# 105358-3SC001-02_CPU_BRD.net
KiCad netlist of a schematic drawn in Altium Designer
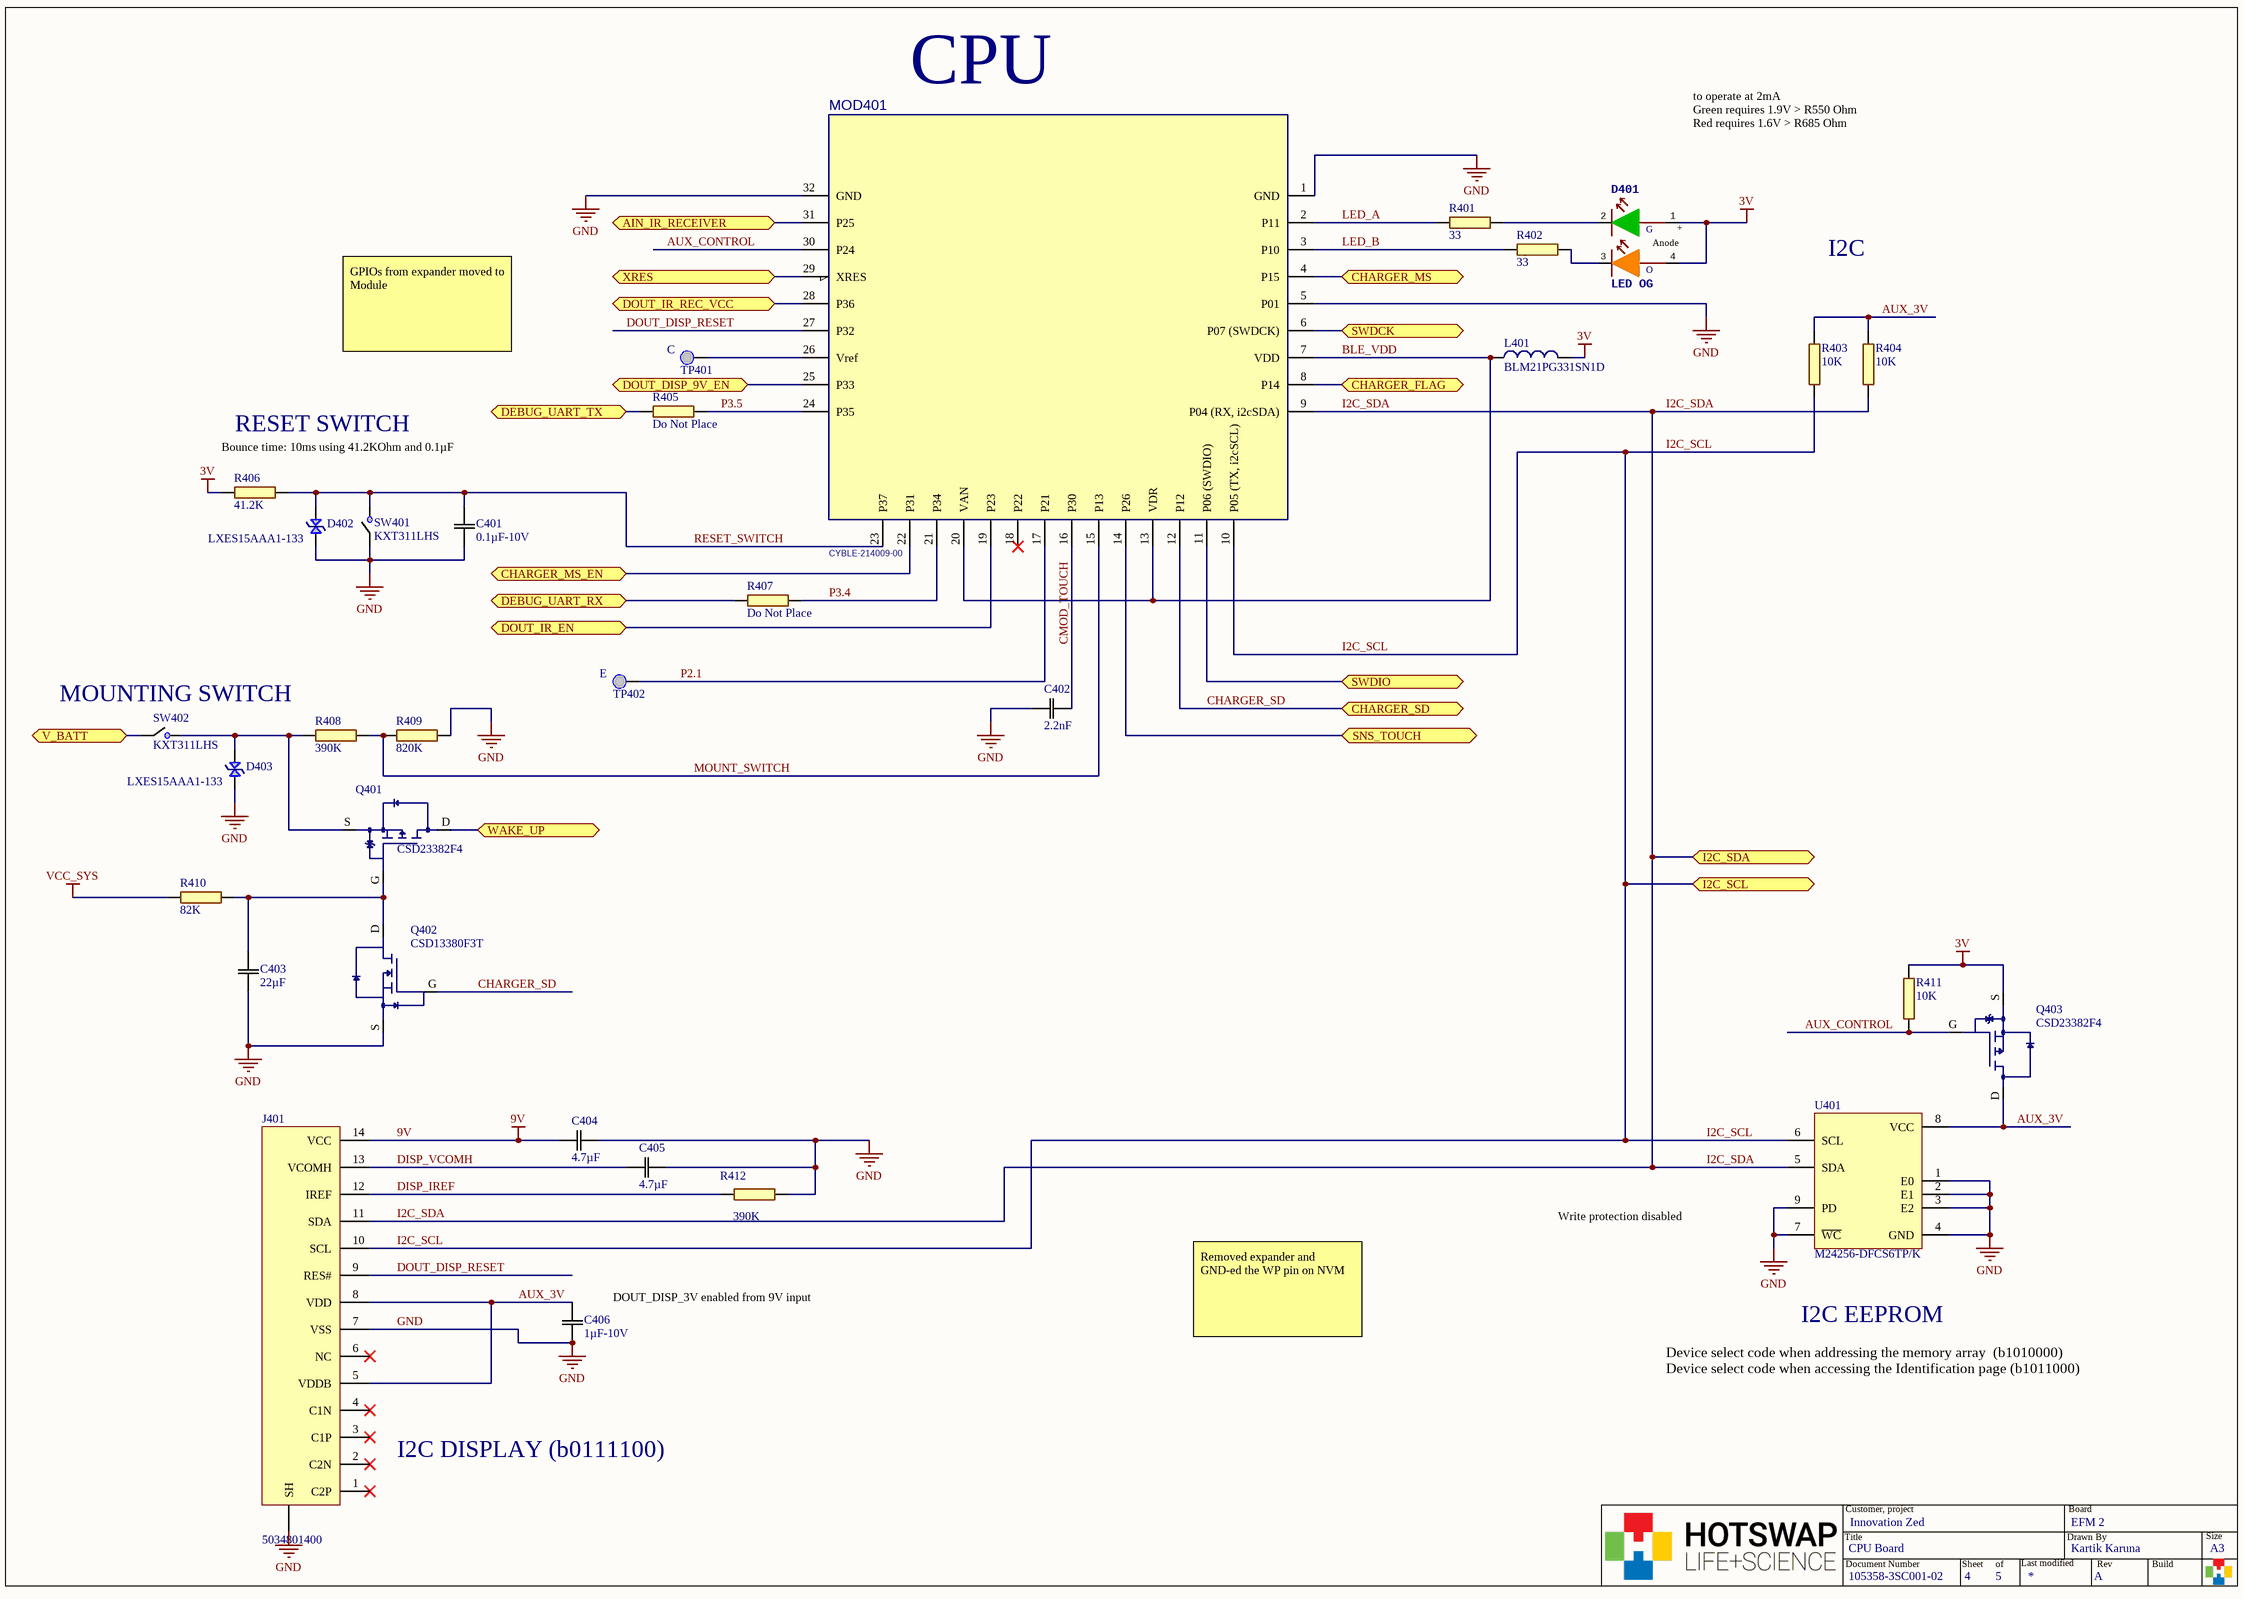
[diagram p0: 105358-3SC001-02_CPU_BRD.SchDoc]

(export (version "E")
  (design (tool "Eeschema 10.0.6"))
  (components
    (comp (ref "C401")
      (value "0.1µF-10V")
      (footprint "0402C_HIGH_DENSITY")
      (description "0.1µF ±10% 10V X5R Ceramic Capacitor 0402")
      (fields
        (field (name "MANUFACTURER PART NUMBER") "CC0402KRX5R6BB104")
        (field (name "MANUFACTURER") "Yageo")
      )
      (libsource (lib "ConnectMedical") (part "0402C-0.1uF-10V"))
    )
    (comp (ref "C402")
      (value "2.2nF")
      (footprint "0402C_HIGH_DENSITY")
      (description "2.2nF ±10% 50V X5R Ceramic Capacitor 0402")
      (fields
        (field (name "MANUFACTURER PART NUMBER") "GRM155R61H222KA01D")
        (field (name "MANUFACTURER") "Murata Electronics North America")
      )
      (libsource (lib "ConnectMedical") (part "0402C-2.2nF-50V"))
    )
    (comp (ref "C403")
      (value "22µF")
      (footprint "0603C-GENERIC")
      (description "22µF ±20% 10V Ceramic Capacitor X5R 0603")
      (fields
        (field (name "MANUFACTURER PART NUMBER") "C1608X5R1A226M080AC")
        (field (name "MANUFACTURER") "TDK Corporation")
      )
      (libsource (lib "ConnectMedical") (part "0603C-22uF-10V"))
    )
    (comp (ref "C404")
      (value "4.7µF")
      (footprint "0402C_HIGH_DENSITY")
      (description "4.7µF ±10% 6.3V X5R Ceramic Capacitor 0402")
      (fields
        (field (name "MANUFACTURER PART NUMBER") "C1005X5R0J475K050BC")
        (field (name "MANUFACTURER") "TDK Corporation")
      )
      (libsource (lib "ConnectMedical") (part "0402C-4.7uF-6.3V"))
    )
    (comp (ref "C405")
      (value "4.7µF")
      (footprint "0402C_HIGH_DENSITY")
      (description "4.7µF ±10% 6.3V X5R Ceramic Capacitor 0402")
      (fields
        (field (name "MANUFACTURER PART NUMBER") "C1005X5R0J475K050BC")
        (field (name "MANUFACTURER") "TDK Corporation")
      )
      (libsource (lib "ConnectMedical") (part "0402C-4.7uF-6.3V"))
    )
    (comp (ref "C406")
      (value "1µF-10V")
      (footprint "0402C_HIGH_DENSITY")
      (description "1µF ±10% 10V X5R Ceramic Capacitor 0402")
      (fields
        (field (name "MANUFACTURER PART NUMBER") "CC0402KRX5R6BB105")
        (field (name "MANUFACTURER") "Yageo")
      )
      (libsource (lib "ConnectMedical") (part "0402C-1uF-10V"))
    )
    (comp (ref "D401")
      (value "LED OG")
      (footprint "KPHBM-2012CGKSEKC")
      (description "LED GRN/ORNG")
      (fields
        (field (name "MANUFACTURER") "Kingbright")
        (field (name "MANUFACTURER PART NUMBER") "KPHBM-2012CGKSEKC")
      )
      (libsource (lib "ConnectMedical") (part "LED GRN/ORNG 570NM 601NM"))
    )
    (comp (ref "D402")
      (value "LXES15AAA1-133")
      (footprint "0402C-GENERIC")
      (description "TVS DIODE 15VWM 0402")
      (fields
        (field (name "MANUFACTURER") "Murata Electronics North America")
        (field (name "DIGI-KEY PART NUMBER") "490-13209-1-ND")
      )
      (libsource (lib "ConnectMedical") (part "TVS DIODE 15VWM 0402"))
    )
    (comp (ref "D403")
      (value "LXES15AAA1-133")
      (footprint "0402C-GENERIC")
      (description "TVS DIODE 15VWM 0402")
      (fields
        (field (name "MANUFACTURER") "Murata Electronics North America")
        (field (name "DIGI-KEY PART NUMBER") "490-13209-1-ND")
      )
      (libsource (lib "ConnectMedical") (part "TVS DIODE 15VWM 0402"))
    )
    (comp (ref "J401")
      (value "5034801400")
      (footprint "5034801400")
      (description "Connector molex to OLED Display")
      (fields (field (name "MANUFACTURER") "Molex, LLC") (field (name "DIGI-KEY PART NUMBER") "WM1442CT-ND"))
      (libsource (lib "ConnectMedical") (part "Molex-5034801400"))
    )
    (comp (ref "L401")
      (value "BLM21PG331SN1D")
      (footprint "0805L_HIGH_DENSITY - Hybrid 0402")
      (description "0805 Ferrite Bead 330Ohm@100MHz")
      (fields
        (field (name "DIGI-KEY PART NUMBER") "490-5988-1-ND")
        (field (name "MANUFACTURER") "Murata Electronics North America")
      )
      (libsource (lib "ConnectMedical") (part "BLM21PG331SN1D"))
    )
    (comp (ref "MOD401")
      (value "CYBLE-214009-00")
      (footprint "CYBLE-014008-00_MinKeepOut")
      (description "BLE PSoC Module 4.1")
      (fields
        (field (name "MANUFACTURER") "Cypress Semiconductor Corp")
        (field (name "DIGI-KEY PART NUMBER") "428-3809-ND")
      )
      (libsource (lib "ConnectMedical") (part "CYBLE-214009-00"))
    )
    (comp (ref "Q401")
      (value "CSD23382F4")
      (footprint "CSD23382F4 -DFN65P100X35-3L")
      (description "MOSFET P-CH 12V 22A 3PICOSTAR")
      (fields
        (field (name "DIGI-KEY PART NUMBER") "296-40003-1-ND")
        (field (name "MANUFACTURER") "Texas Instruments")
      )
      (libsource (lib "ConnectMedical") (part "CSD23382F4"))
    )
    (comp (ref "Q402")
      (value "CSD13380F3T")
      (footprint "CSD13380F3-DFN40P69X35-3L")
      (description "12V N-CHANNEL FEMTOFET MOSFET")
      (fields (field (name "MANUFACTURER") "Texas Instruments"))
      (libsource (lib "ConnectMedical") (part "CSD13380F3T"))
    )
    (comp (ref "Q403")
      (value "CSD23382F4")
      (footprint "CSD23382F4 -DFN65P100X35-3L")
      (description "MOSFET P-CH 12V 22A 3PICOSTAR")
      (fields
        (field (name "DIGI-KEY PART NUMBER") "296-40003-1-ND")
        (field (name "MANUFACTURER") "Texas Instruments")
      )
      (libsource (lib "ConnectMedical") (part "CSD23382F4"))
    )
    (comp (ref "R401")
      (value "33")
      (footprint "0402R-GENERIC")
      (description "RES SMD  33 OHM 1% 1/16W 0402")
      (fields (field (name "DIGI-KEY PART NUMBER") "311-33.0LRCT-ND") (field (name "MANUFACTURER") "Yageo"))
      (libsource (lib "ConnectMedical") (part "0402R- 33 OHM-1%-0.063W"))
    )
    (comp (ref "R402")
      (value "33")
      (footprint "0402R-GENERIC")
      (description "RES SMD  33 OHM 1% 1/16W 0402")
      (fields (field (name "DIGI-KEY PART NUMBER") "311-33.0LRCT-ND") (field (name "MANUFACTURER") "Yageo"))
      (libsource (lib "ConnectMedical") (part "0402R- 33 OHM-1%-0.063W"))
    )
    (comp (ref "R403")
      (value "10K")
      (footprint "0402R-GENERIC")
      (description "RES SMD 10kOHM 1% 1/16W 0402")
      (fields (field (name "DIGI-KEY PART NUMBER") "311-10.0KLRCT-ND") (field (name "MANUFACTURER") "Yageo"))
      (libsource (lib "ConnectMedical") (part "0402R-10k OHM-1%-0.063W"))
    )
    (comp (ref "R404")
      (value "10K")
      (footprint "0402R-GENERIC")
      (description "RES SMD 10kOHM 1% 1/16W 0402")
      (fields (field (name "DIGI-KEY PART NUMBER") "311-10.0KLRCT-ND") (field (name "MANUFACTURER") "Yageo"))
      (libsource (lib "ConnectMedical") (part "0402R-10k OHM-1%-0.063W"))
    )
    (comp (ref "R405")
      (value "Do Not Place")
      (footprint "0402R-GENERIC")
      (libsource (lib "ConnectMedical") (part "0402R-Do Not Place"))
    )
    (comp (ref "R406")
      (value "41.2K")
      (footprint "0402R-GENERIC")
      (description "RES SMD 41.2kOHM 1% 1/16W 0402")
      (fields (field (name "DIGI-KEY PART NUMBER") "YAG3155CT-ND") (field (name "MANUFACTURER") "Yageo"))
      (libsource (lib "ConnectMedical") (part "0402R-41.2k OHM-1%-0.063W"))
    )
    (comp (ref "R407")
      (value "Do Not Place")
      (footprint "0402R-GENERIC")
      (libsource (lib "ConnectMedical") (part "0402R-Do Not Place"))
    )
    (comp (ref "R408")
      (value "390K")
      (footprint "0402R-GENERIC")
      (description "RES SMD 390kOHM 1% 1/16W 0402")
      (fields (field (name "DIGI-KEY PART NUMBER") "YAG3143CT-ND") (field (name "MANUFACTURER") "Yageo"))
      (libsource (lib "ConnectMedical") (part "0402R-390k OHM-1%-0.063W"))
    )
    (comp (ref "R409")
      (value "820K")
      (footprint "0402R-GENERIC")
      (description "RES SMD 820kOHM 1% 1/16W 0402")
      (fields (field (name "DIGI-KEY PART NUMBER") "YAG3240CT-ND") (field (name "MANUFACTURER") "Yageo"))
      (libsource (lib "ConnectMedical") (part "0402R-820k OHM-1%-0.063W"))
    )
    (comp (ref "R410")
      (value "82K")
      (footprint "0402R-GENERIC")
      (description "RES SMD 82kOHM 1% 1/16W 0402")
      (fields (field (name "DIGI-KEY PART NUMBER") "311-82.0KLRCT-ND") (field (name "MANUFACTURER") "Yageo"))
      (libsource (lib "ConnectMedical") (part "0402R-82k OHM-1%-0.063W"))
    )
    (comp (ref "R411")
      (value "10K")
      (footprint "0402R-GENERIC")
      (description "RES SMD 10kOHM 1% 1/16W 0402")
      (fields (field (name "DIGI-KEY PART NUMBER") "311-10.0KLRCT-ND") (field (name "MANUFACTURER") "Yageo"))
      (libsource (lib "ConnectMedical") (part "0402R-10k OHM-1%-0.063W"))
    )
    (comp (ref "R412")
      (value "390K")
      (footprint "0402R-GENERIC")
      (description "RES SMD 390kOHM 1% 1/16W 0402")
      (fields (field (name "DIGI-KEY PART NUMBER") "YAG3143CT-ND") (field (name "MANUFACTURER") "Yageo"))
      (libsource (lib "ConnectMedical") (part "0402R-390k OHM-1%-0.063W"))
    )
    (comp (ref "SW401")
      (value "KXT311LHS")
      (footprint "KXT311LHS_B")
      (description "SPST Tactile Switch")
      (fields (field (name "MANUFACTURER PART NUMBER") "KXT 311 LHS") (field (name "MANUFACTURER") "C&K"))
      (libsource (lib "ConnectMedical") (part "KXT311LHS"))
    )
    (comp (ref "SW402")
      (value "KXT311LHS")
      (footprint "KXT311LHS_B")
      (description "SPST Tactile Switch")
      (fields (field (name "MANUFACTURER PART NUMBER") "KXT 311 LHS") (field (name "MANUFACTURER") "C&K"))
      (libsource (lib "ConnectMedical") (part "KXT311LHS"))
    )
    (comp (ref "TP401")
      (value "TEST POINT")
      (footprint "PAD TEST POINT")
      (description "Testing Poiny")
      (libsource (lib "ConnectMedical") (part "TEST POINT"))
    )
    (comp (ref "TP402")
      (value "TEST POINT")
      (footprint "PAD TEST POINT")
      (description "Testing Poiny")
      (libsource (lib "ConnectMedical") (part "TEST POINT"))
    )
    (comp (ref "U401")
      (value "M24256-DFCS6TP/K")
      (footprint "UFDFPN8-M24256-DFMC6TG")
      (description "IC EEPROM 256KBIT 400KHZ 8UFDFPN")
      (fields
        (field (name "MANUFACTURER PART NUMBER") "M24256-DFMC6TG")
        (field (name "MANUFACTURER") "STMicroelectronics")
      )
      (libsource (lib "ConnectMedical") (part "M24256-DFMC6TG"))
    )
  )
  (nets
    (net (code "1") (name "/AIN_IR_RECEIVER") (class "Default")
      (node (ref "MOD401") (pin "31") (pinfunction "P25_31") (pintype "passive"))
    )
    (net (code "2") (name "/AUX_3V") (class "Default")
      (node (ref "C406") (pin "2") (pinfunction "2_2") (pintype "passive"))
      (node (ref "J401") (pin "5") (pinfunction "VDDB_5") (pintype "passive"))
      (node (ref "J401") (pin "8") (pinfunction "VDD_8") (pintype "passive"))
      (node (ref "Q403") (pin "D") (pinfunction "3_D") (pintype "passive"))
      (node (ref "R403") (pin "1") (pintype "passive"))
      (node (ref "R404") (pin "1") (pintype "passive"))
      (node (ref "U401") (pin "8") (pinfunction "VCC_8") (pintype "passive"))
    )
    (net (code "3") (name "/AUX_CONTROL") (class "Default")
      (node (ref "MOD401") (pin "30") (pinfunction "P24_30") (pintype "passive"))
      (node (ref "Q403") (pin "G") (pinfunction "1_G") (pintype "passive"))
      (node (ref "R411") (pin "2") (pintype "passive"))
    )
    (net (code "4") (name "/BLE_VDD") (class "Default")
      (node (ref "L401") (pin "1") (pinfunction "1_1") (pintype "passive"))
      (node (ref "MOD401") (pin "13") (pinfunction "VDR_13") (pintype "power_in"))
      (node (ref "MOD401") (pin "20") (pinfunction "VAN_20") (pintype "power_in"))
      (node (ref "MOD401") (pin "7") (pinfunction "VDD_7") (pintype "power_in"))
    )
    (net (code "5") (name "/CHARGER_FLAG") (class "Default")
      (node (ref "MOD401") (pin "8") (pinfunction "P14_8") (pintype "passive"))
    )
    (net (code "6") (name "/CHARGER_MS") (class "Default")
      (node (ref "MOD401") (pin "4") (pinfunction "P15_4") (pintype "passive"))
    )
    (net (code "7") (name "/CHARGER_MS_EN") (class "Default")
      (node (ref "MOD401") (pin "22") (pinfunction "P31_22") (pintype "passive"))
    )
    (net (code "8") (name "/CHARGER_SD") (class "Default")
      (node (ref "MOD401") (pin "12") (pinfunction "P12_12") (pintype "passive"))
      (node (ref "Q402") (pin "G") (pinfunction "1_G") (pintype "passive"))
    )
    (net (code "9") (name "/CMOD_TOUCH") (class "Default")
      (node (ref "C402") (pin "1") (pinfunction "1_1") (pintype "passive"))
      (node (ref "MOD401") (pin "16") (pinfunction "P30_16") (pintype "passive"))
    )
    (net (code "10") (name "/DEBUG_UART_RX") (class "Default")
      (node (ref "R407") (pin "1") (pintype "passive"))
    )
    (net (code "11") (name "/DEBUG_UART_TX") (class "Default")
      (node (ref "R405") (pin "1") (pintype "passive"))
    )
    (net (code "12") (name "/DISP_IREF") (class "Default")
      (node (ref "J401") (pin "12") (pinfunction "IREF_12") (pintype "passive"))
      (node (ref "R412") (pin "1") (pintype "passive"))
    )
    (net (code "13") (name "/DISP_VCOMH") (class "Default")
      (node (ref "C405") (pin "2") (pinfunction "2_2") (pintype "passive"))
      (node (ref "J401") (pin "13") (pinfunction "VCOMH_13") (pintype "passive"))
    )
    (net (code "14") (name "/DOUT_DISP_9V_EN") (class "Default")
      (node (ref "MOD401") (pin "25") (pinfunction "P33_25") (pintype "passive"))
    )
    (net (code "15") (name "/DOUT_DISP_RESET") (class "Default")
      (node (ref "J401") (pin "9") (pinfunction "RES#_9") (pintype "passive"))
      (node (ref "MOD401") (pin "27") (pinfunction "P32_27") (pintype "passive"))
    )
    (net (code "16") (name "/DOUT_IR_EN") (class "Default")
      (node (ref "MOD401") (pin "19") (pinfunction "P23_19") (pintype "passive"))
    )
    (net (code "17") (name "/DOUT_IR_REC_VCC") (class "Default")
      (node (ref "MOD401") (pin "28") (pinfunction "P36_28") (pintype "passive"))
    )
    (net (code "18") (name "/I2C_SCL") (class "Default")
      (node (ref "J401") (pin "10") (pinfunction "SCL_10") (pintype "passive"))
      (node (ref "MOD401") (pin "10") (pinfunction "P05_(TX,_i2cSCL)_10") (pintype "passive"))
      (node (ref "R403") (pin "2") (pintype "passive"))
      (node (ref "U401") (pin "6") (pinfunction "SCL_6") (pintype "passive"))
    )
    (net (code "19") (name "/I2C_SDA") (class "Default")
      (node (ref "J401") (pin "11") (pinfunction "SDA_11") (pintype "passive"))
      (node (ref "MOD401") (pin "9") (pinfunction "P04_(RX,_i2cSDA)_9") (pintype "passive"))
      (node (ref "R404") (pin "2") (pintype "passive"))
      (node (ref "U401") (pin "5") (pinfunction "SDA_5") (pintype "passive"))
    )
    (net (code "20") (name "/LED_A") (class "Default")
      (node (ref "MOD401") (pin "2") (pinfunction "P11_2") (pintype "passive"))
      (node (ref "R401") (pin "1") (pintype "passive"))
    )
    (net (code "21") (name "/LED_B") (class "Default")
      (node (ref "MOD401") (pin "3") (pinfunction "P10_3") (pintype "passive"))
      (node (ref "R402") (pin "1") (pintype "passive"))
    )
    (net (code "22") (name "/MOUNT_SWITCH") (class "Default")
      (node (ref "MOD401") (pin "15") (pinfunction "P13_15") (pintype "passive"))
      (node (ref "R408") (pin "2") (pintype "passive"))
      (node (ref "R409") (pin "2") (pintype "passive"))
    )
    (net (code "23") (name "/P2.1") (class "Default")
      (node (ref "MOD401") (pin "17") (pinfunction "P21_17") (pintype "passive"))
      (node (ref "TP402") (pin "1") (pinfunction "Test_Point_1") (pintype "passive"))
    )
    (net (code "24") (name "/P3.4") (class "Default")
      (node (ref "MOD401") (pin "21") (pinfunction "P34_21") (pintype "passive"))
      (node (ref "R407") (pin "2") (pintype "passive"))
    )
    (net (code "25") (name "/P3.5") (class "Default")
      (node (ref "MOD401") (pin "24") (pinfunction "P35_24") (pintype "passive"))
      (node (ref "R405") (pin "2") (pintype "passive"))
    )
    (net (code "26") (name "/RESET_SWITCH") (class "Default")
      (node (ref "C401") (pin "2") (pinfunction "2_2") (pintype "passive"))
      (node (ref "D402") (pin "2") (pinfunction "2_2") (pintype "passive"))
      (node (ref "MOD401") (pin "23") (pinfunction "P37_23") (pintype "passive"))
      (node (ref "R406") (pin "2") (pintype "passive"))
      (node (ref "SW401") (pin "2") (pinfunction "2_2") (pintype "passive"))
    )
    (net (code "27") (name "/SNS_TOUCH") (class "Default")
      (node (ref "MOD401") (pin "14") (pinfunction "P26_14") (pintype "passive"))
    )
    (net (code "28") (name "/SWDCK") (class "Default")
      (node (ref "MOD401") (pin "6") (pinfunction "P07_(SWDCK)_6") (pintype "passive"))
    )
    (net (code "29") (name "/SWDIO") (class "Default")
      (node (ref "MOD401") (pin "11") (pinfunction "P06_(SWDIO)_11") (pintype "passive"))
    )
    (net (code "30") (name "/V_BATT") (class "Default")
      (node (ref "SW402") (pin "1") (pinfunction "1_1") (pintype "passive"))
    )
    (net (code "31") (name "/WAKE_UP") (class "Default")
      (node (ref "Q401") (pin "D") (pinfunction "3_D") (pintype "passive"))
    )
    (net (code "32") (name "/XRES") (class "Default")
      (node (ref "MOD401") (pin "29") (pinfunction "XRES_29") (pintype "passive"))
    )
    (net (code "33") (name "3V") (class "Default")
      (node (ref "D401") (pin "1") (pinfunction "1_1") (pintype "passive"))
      (node (ref "D401") (pin "4") (pinfunction "4_4") (pintype "passive"))
      (node (ref "L401") (pin "2") (pinfunction "2_2") (pintype "passive"))
      (node (ref "Q403") (pin "S") (pinfunction "2_S") (pintype "passive"))
      (node (ref "R406") (pin "1") (pintype "passive"))
      (node (ref "R411") (pin "1") (pintype "passive"))
    )
    (net (code "34") (name "9V") (class "Default")
      (node (ref "C404") (pin "1") (pinfunction "1_1") (pintype "passive"))
      (node (ref "J401") (pin "14") (pinfunction "VCC_14") (pintype "passive"))
    )
    (net (code "35") (name "GND") (class "Default")
      (node (ref "C401") (pin "1") (pinfunction "1_1") (pintype "passive"))
      (node (ref "C402") (pin "2") (pinfunction "2_2") (pintype "passive"))
      (node (ref "C403") (pin "1") (pinfunction "1_1") (pintype "passive"))
      (node (ref "C404") (pin "2") (pinfunction "2_2") (pintype "passive"))
      (node (ref "C405") (pin "1") (pinfunction "1_1") (pintype "passive"))
      (node (ref "C406") (pin "1") (pinfunction "1_1") (pintype "passive"))
      (node (ref "D402") (pin "1") (pinfunction "1_1") (pintype "passive"))
      (node (ref "D403") (pin "1") (pinfunction "1_1") (pintype "passive"))
      (node (ref "J401") (pin "7") (pinfunction "VSS_7") (pintype "power_in"))
      (node (ref "J401") (pin "SH") (pinfunction "SH_SH") (pintype "passive"))
      (node (ref "MOD401") (pin "1") (pinfunction "GND_1") (pintype "power_in"))
      (node (ref "MOD401") (pin "32") (pinfunction "GND_32") (pintype "power_in"))
      (node (ref "MOD401") (pin "5") (pinfunction "P01_5") (pintype "passive"))
      (node (ref "Q402") (pin "S") (pinfunction "2_S") (pintype "passive"))
      (node (ref "R409") (pin "1") (pintype "passive"))
      (node (ref "R412") (pin "2") (pintype "passive"))
      (node (ref "SW401") (pin "1") (pinfunction "1_1") (pintype "passive"))
      (node (ref "U401") (pin "1") (pinfunction "E0_1") (pintype "passive"))
      (node (ref "U401") (pin "2") (pinfunction "E1_2") (pintype "passive"))
      (node (ref "U401") (pin "3") (pinfunction "E2_3") (pintype "passive"))
      (node (ref "U401") (pin "4") (pinfunction "GND_4") (pintype "passive"))
      (node (ref "U401") (pin "7") (pinfunction "~{WC}_7") (pintype "passive"))
      (node (ref "U401") (pin "9") (pinfunction "PD_9") (pintype "passive"))
    )
    (net (code "36") (name "Net-(D401-G)") (class "Default")
      (node (ref "D401") (pin "2") (pinfunction "G_2") (pintype "passive"))
      (node (ref "R401") (pin "2") (pintype "passive"))
    )
    (net (code "37") (name "Net-(D401-Pad3)") (class "Default")
      (node (ref "D401") (pin "3") (pinfunction "3_3") (pintype "passive"))
      (node (ref "R402") (pin "2") (pintype "passive"))
    )
    (net (code "38") (name "Net-(MOD401-Vref)") (class "Default")
      (node (ref "MOD401") (pin "26") (pinfunction "Vref_26") (pintype "power_in"))
      (node (ref "TP401") (pin "1") (pinfunction "Test_Point_1") (pintype "passive"))
    )
    (net (code "39") (name "Net-(Q401-1)") (class "Default")
      (node (ref "C403") (pin "2") (pinfunction "2_2") (pintype "passive"))
      (node (ref "Q401") (pin "G") (pinfunction "1_G") (pintype "passive"))
      (node (ref "Q402") (pin "D") (pinfunction "3_D") (pintype "passive"))
      (node (ref "R410") (pin "2") (pintype "passive"))
    )
    (net (code "40") (name "Net-(Q401-2)") (class "Default")
      (node (ref "D403") (pin "2") (pinfunction "2_2") (pintype "passive"))
      (node (ref "Q401") (pin "S") (pinfunction "2_S") (pintype "passive"))
      (node (ref "R408") (pin "1") (pintype "passive"))
      (node (ref "SW402") (pin "2") (pinfunction "2_2") (pintype "passive"))
    )
    (net (code "41") (name "VCC_SYS") (class "Default") (node (ref "R410") (pin "1") (pintype "passive")))
    (net (code "42") (name "unconnected-(J401-C1N-Pad4)") (class "Default")
      (node (ref "J401") (pin "4") (pinfunction "C1N_4") (pintype "passive+no_connect"))
    )
    (net (code "43") (name "unconnected-(J401-C1P-Pad3)") (class "Default")
      (node (ref "J401") (pin "3") (pinfunction "C1P_3") (pintype "passive+no_connect"))
    )
    (net (code "44") (name "unconnected-(J401-C2N-Pad2)") (class "Default")
      (node (ref "J401") (pin "2") (pinfunction "C2N_2") (pintype "passive+no_connect"))
    )
    (net (code "45") (name "unconnected-(J401-C2P-Pad1)") (class "Default")
      (node (ref "J401") (pin "1") (pinfunction "C2P_1") (pintype "passive+no_connect"))
    )
    (net (code "46") (name "unconnected-(J401-NC-Pad6)") (class "Default")
      (node (ref "J401") (pin "6") (pinfunction "NC_6") (pintype "passive+no_connect"))
    )
    (net (code "47") (name "unconnected-(MOD401-P22-Pad18)") (class "Default")
      (node (ref "MOD401") (pin "18") (pinfunction "P22_18") (pintype "passive+no_connect"))
    )
  )
)
